# Ant_Robot_Controller.net
KiCad netlist of a schematic drawn in Altium Designer
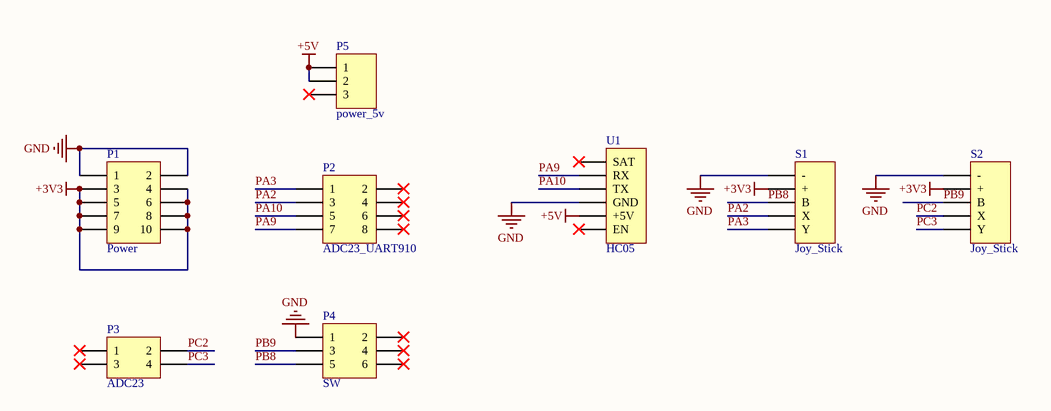
[diagram p0: Ant_Robot_Controller.SchDoc]

(export (version "E")
  (design (tool "Eeschema 10.0.6"))
  (components
    (comp (ref "P1")
      (value "Power")
      (footprint "HDR2X5")
      (description "Header, 5-Pin, Dual row")
      (fields (field (name "PUBLISHER") "Altium Limited"))
      (libsource (lib "Miscellaneous Connectors") (part "Header 5X2"))
    )
    (comp (ref "P2")
      (value "ADC23_UART910")
      (footprint "HDR2X4")
      (description "Header, 4-Pin, Dual row")
      (fields (field (name "PUBLISHER") "Altium Limited"))
      (libsource (lib "Miscellaneous Connectors") (part "Header 4X2"))
    )
    (comp (ref "P3")
      (value "ADC23")
      (footprint "HDR2X2")
      (description "Header, 2-Pin, Dual row")
      (fields (field (name "PUBLISHER") "Altium Limited"))
      (libsource (lib "Miscellaneous Connectors") (part "Header 2X2"))
    )
    (comp (ref "P4")
      (value "SW")
      (footprint "HDR2X3")
      (description "Header, 3-Pin, Dual row")
      (fields (field (name "PUBLISHER") "Altium Limited"))
      (libsource (lib "Miscellaneous Connectors") (part "Header 3X2"))
    )
    (comp (ref "P5")
      (value "power_5v")
      (footprint "HDR1X3")
      (description "Header, 3-Pin")
      (fields (field (name "PUBLISHER") "Altium Limited"))
      (libsource (lib "零件庫") (part "Header 3"))
    )
    (comp (ref "S1")
      (value "Joy_Stick")
      (footprint "HDR1X5")
      (description "Header, 5-Pin")
      (fields (field (name "PUBLISHER") "Altium Limited"))
      (libsource (lib "零件庫") (part "Header 5"))
    )
    (comp (ref "S2")
      (value "Joy_Stick")
      (footprint "HDR1X5")
      (description "Header, 5-Pin")
      (fields (field (name "PUBLISHER") "Altium Limited"))
      (libsource (lib "零件庫") (part "Header 5"))
    )
    (comp (ref "U1")
      (value "HC05")
      (footprint "HDR1X6")
      (description "Header, 6-Pin")
      (fields (field (name "PUBLISHER") "Altium Limited"))
      (libsource (lib "零件庫") (part "Header 6"))
    )
  )
  (nets
    (net (code "1") (name "+3V3") (class "Default")
      (node (ref "P1") (pin "10") (pinfunction "10_10") (pintype "passive"))
      (node (ref "P1") (pin "3") (pinfunction "3_3") (pintype "passive"))
      (node (ref "P1") (pin "4") (pinfunction "4_4") (pintype "passive"))
      (node (ref "P1") (pin "5") (pinfunction "5_5") (pintype "passive"))
      (node (ref "P1") (pin "6") (pinfunction "6_6") (pintype "passive"))
      (node (ref "P1") (pin "7") (pinfunction "7_7") (pintype "passive"))
      (node (ref "P1") (pin "8") (pinfunction "8_8") (pintype "passive"))
      (node (ref "P1") (pin "9") (pinfunction "9_9") (pintype "passive"))
      (node (ref "S1") (pin "2") (pinfunction "+_2") (pintype "passive"))
      (node (ref "S2") (pin "2") (pinfunction "+_2") (pintype "passive"))
    )
    (net (code "2") (name "+5V") (class "Default")
      (node (ref "P5") (pin "1") (pinfunction "1_1") (pintype "passive"))
      (node (ref "P5") (pin "2") (pinfunction "2_2") (pintype "passive"))
      (node (ref "U1") (pin "5") (pinfunction "+5V_5") (pintype "passive"))
    )
    (net (code "3") (name "/PA2") (class "Default")
      (node (ref "P2") (pin "3") (pinfunction "3_3") (pintype "passive"))
      (node (ref "S1") (pin "4") (pinfunction "X_4") (pintype "passive"))
    )
    (net (code "4") (name "/PA3") (class "Default")
      (node (ref "P2") (pin "1") (pinfunction "1_1") (pintype "passive"))
      (node (ref "S1") (pin "5") (pinfunction "Y_5") (pintype "passive"))
    )
    (net (code "5") (name "/PA9") (class "Default")
      (node (ref "P2") (pin "7") (pinfunction "7_7") (pintype "passive"))
      (node (ref "U1") (pin "2") (pinfunction "RX_2") (pintype "passive"))
    )
    (net (code "6") (name "/PA10") (class "Default")
      (node (ref "P2") (pin "5") (pinfunction "5_5") (pintype "passive"))
      (node (ref "U1") (pin "3") (pinfunction "TX_3") (pintype "passive"))
    )
    (net (code "7") (name "/PB8") (class "Default")
      (node (ref "P4") (pin "5") (pinfunction "5_5") (pintype "passive"))
      (node (ref "S1") (pin "3") (pinfunction "B_3") (pintype "passive"))
    )
    (net (code "8") (name "/PB9") (class "Default")
      (node (ref "P4") (pin "3") (pinfunction "3_3") (pintype "passive"))
      (node (ref "S2") (pin "3") (pinfunction "B_3") (pintype "passive"))
    )
    (net (code "9") (name "/PC2") (class "Default")
      (node (ref "P3") (pin "2") (pinfunction "2_2") (pintype "passive"))
      (node (ref "S2") (pin "4") (pinfunction "X_4") (pintype "passive"))
    )
    (net (code "10") (name "/PC3") (class "Default")
      (node (ref "P3") (pin "4") (pinfunction "4_4") (pintype "passive"))
      (node (ref "S2") (pin "5") (pinfunction "Y_5") (pintype "passive"))
    )
    (net (code "11") (name "GND") (class "Default")
      (node (ref "P1") (pin "1") (pinfunction "1_1") (pintype "passive"))
      (node (ref "P1") (pin "2") (pinfunction "2_2") (pintype "passive"))
      (node (ref "P4") (pin "1") (pinfunction "1_1") (pintype "passive"))
      (node (ref "S1") (pin "1") (pinfunction "-_1") (pintype "passive"))
      (node (ref "S2") (pin "1") (pinfunction "-_1") (pintype "passive"))
      (node (ref "U1") (pin "4") (pinfunction "GND_4") (pintype "passive"))
    )
    (net (code "12") (name "unconnected-(P2-Pad2)") (class "Default")
      (node (ref "P2") (pin "2") (pinfunction "2_2") (pintype "passive+no_connect"))
    )
    (net (code "13") (name "unconnected-(P2-Pad4)") (class "Default")
      (node (ref "P2") (pin "4") (pinfunction "4_4") (pintype "passive+no_connect"))
    )
    (net (code "14") (name "unconnected-(P2-Pad6)") (class "Default")
      (node (ref "P2") (pin "6") (pinfunction "6_6") (pintype "passive+no_connect"))
    )
    (net (code "15") (name "unconnected-(P2-Pad8)") (class "Default")
      (node (ref "P2") (pin "8") (pinfunction "8_8") (pintype "passive+no_connect"))
    )
    (net (code "16") (name "unconnected-(P3-Pad1)") (class "Default")
      (node (ref "P3") (pin "1") (pinfunction "1_1") (pintype "passive+no_connect"))
    )
    (net (code "17") (name "unconnected-(P3-Pad3)") (class "Default")
      (node (ref "P3") (pin "3") (pinfunction "3_3") (pintype "passive+no_connect"))
    )
    (net (code "18") (name "unconnected-(P4-Pad2)") (class "Default")
      (node (ref "P4") (pin "2") (pinfunction "2_2") (pintype "passive+no_connect"))
    )
    (net (code "19") (name "unconnected-(P4-Pad4)") (class "Default")
      (node (ref "P4") (pin "4") (pinfunction "4_4") (pintype "passive+no_connect"))
    )
    (net (code "20") (name "unconnected-(P4-Pad6)") (class "Default")
      (node (ref "P4") (pin "6") (pinfunction "6_6") (pintype "passive+no_connect"))
    )
    (net (code "21") (name "unconnected-(P5-Pad3)") (class "Default")
      (node (ref "P5") (pin "3") (pinfunction "3_3") (pintype "passive+no_connect"))
    )
    (net (code "22") (name "unconnected-(U1-EN-Pad6)") (class "Default")
      (node (ref "U1") (pin "6") (pinfunction "EN_6") (pintype "passive+no_connect"))
    )
    (net (code "23") (name "unconnected-(U1-SAT-Pad1)") (class "Default")
      (node (ref "U1") (pin "1") (pinfunction "SAT_1") (pintype "passive+no_connect"))
    )
  )
)
